# oshi-fuse-board-mk-1_2-mini-ato.net
KiCad netlist of a schematic drawn in EAGLE
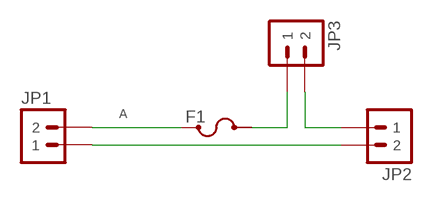
[diagram p0: schematic, sheet 1]

(export (version "E")
  (design (tool "Eeschema 10.0.6"))
  (components
    (comp (ref "F1")
      (value "FUSEMINI-897")
      (footprint "eagle-import:KEYSTONE-MINI-897-FUSE-HOLDER")
      (libsource (lib "eagle-import") (part "FUSEMINI-897"))
    )
    (comp (ref "JP1")
      (value "M025MM")
      (footprint "eagle-import:SCREWTERMINAL-5MM-2")
      (libsource (lib "eagle-import") (part "M025MM"))
    )
    (comp (ref "JP2")
      (value "M025MM")
      (footprint "eagle-import:SCREWTERMINAL-5MM-2")
      (libsource (lib "eagle-import") (part "M025MM"))
    )
    (comp (ref "JP3")
      (value "M025MM")
      (footprint "eagle-import:SCREWTERMINAL-5MM-2")
      (libsource (lib "eagle-import") (part "M025MM"))
    )
  )
  (nets
    (net (code "1") (name "/A") (class "Default")
      (node (ref "F1") (pin "P1@1") (pinfunction "1_P1@1") (pintype "passive"))
      (node (ref "F1") (pin "P1@2") (pinfunction "1_P1@2") (pintype "passive"))
      (node (ref "JP1") (pin "2") (pinfunction "2_2") (pintype "passive"))
    )
    (net (code "2") (name "Net-(F1-2-PadP2@1)") (class "Default")
      (node (ref "F1") (pin "P2@1") (pinfunction "2_P2@1") (pintype "passive"))
      (node (ref "F1") (pin "P2@2") (pinfunction "2_P2@2") (pintype "passive"))
      (node (ref "JP3") (pin "1") (pinfunction "1_1") (pintype "passive"))
    )
    (net (code "3") (name "Net-(JP1-Pad1)") (class "Default")
      (node (ref "JP1") (pin "1") (pinfunction "1_1") (pintype "passive"))
      (node (ref "JP2") (pin "2") (pinfunction "2_2") (pintype "passive"))
    )
    (net (code "4") (name "Net-(JP2-Pad1)") (class "Default")
      (node (ref "JP2") (pin "1") (pinfunction "1_1") (pintype "passive"))
      (node (ref "JP3") (pin "2") (pinfunction "2_2") (pintype "passive"))
    )
  )
)
